# untitled.net
KiCad netlist of a schematic drawn in EAGLE
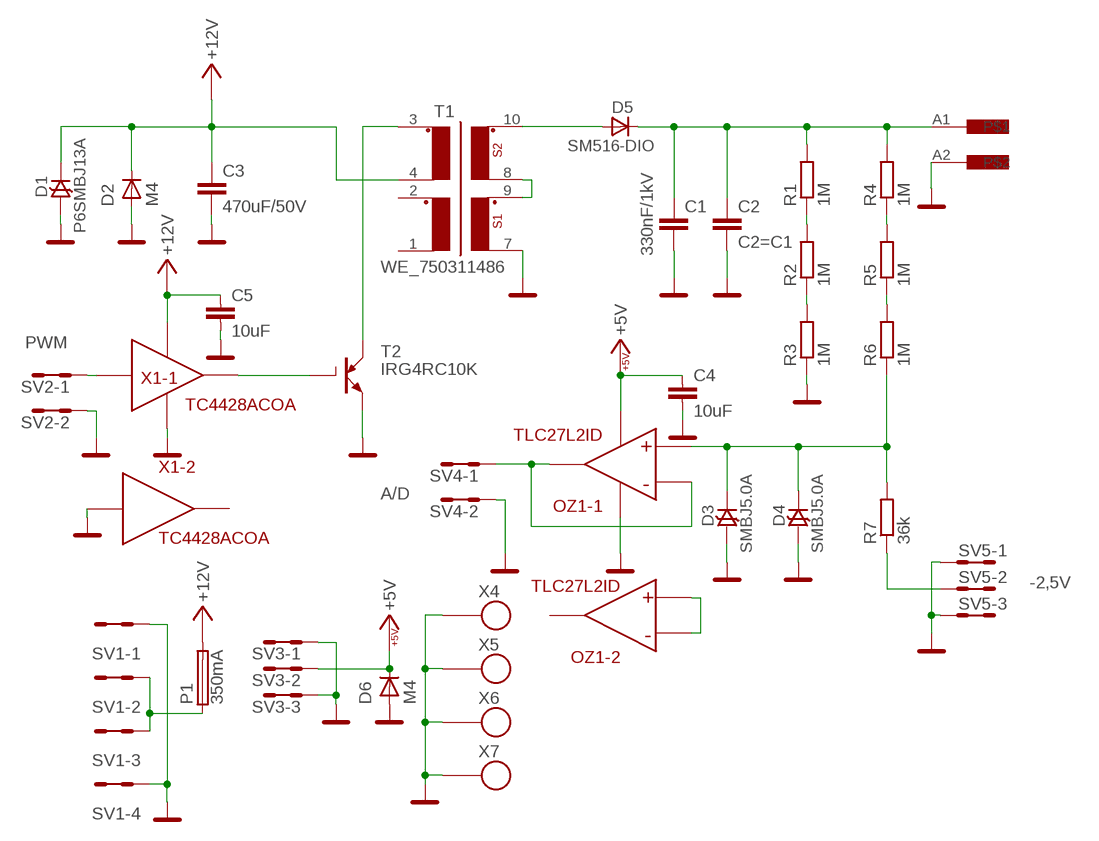
[diagram p0: schematic, sheet 1]

(export (version "E")
  (design (tool "Eeschema 10.0.6"))
  (components
    (comp (ref "C1")
      (value "330nF/1kV")
      (footprint "eagle-import:C22,5MM")
      (libsource (lib "eagle-import") (part "C-22,5MM"))
    )
    (comp (ref "C2")
      (value "C2=C1")
      (footprint "eagle-import:C27,5MM")
      (libsource (lib "eagle-import") (part "C-27,5MM"))
    )
    (comp (ref "C3")
      (value "470uF/50V")
      (footprint "eagle-import:C050-025X075")
      (libsource (lib "eagle-import") (part "C-EU050-025X075"))
    )
    (comp (ref "C4")
      (value "10uF")
      (footprint "eagle-import:C0805")
      (libsource (lib "eagle-import") (part "C0805"))
    )
    (comp (ref "C5")
      (value "10uF")
      (footprint "eagle-import:C0805")
      (libsource (lib "eagle-import") (part "C0805"))
    )
    (comp (ref "D1")
      (value "P6SMBJ13A")
      (footprint "eagle-import:SMB")
      (libsource (lib "eagle-import") (part "D-TRANSIL"))
    )
    (comp (ref "D2")
      (value "M4")
      (footprint "eagle-import:SMA")
      (libsource (lib "eagle-import") (part "D-OB.SMA"))
    )
    (comp (ref "D3")
      (value "SMBJ5.0A")
      (footprint "eagle-import:SMA")
      (libsource (lib "eagle-import") (part "D-TRANSIL-SMA"))
    )
    (comp (ref "D4")
      (value "SMBJ5.0A")
      (footprint "eagle-import:SMA")
      (libsource (lib "eagle-import") (part "D-TRANSIL-SMA"))
    )
    (comp (ref "D5")
      (value "SM516-DIO")
      (footprint "eagle-import:MELF")
      (libsource (lib "eagle-import") (part "D-OB-MELF"))
    )
    (comp (ref "D6")
      (value "M4")
      (footprint "eagle-import:SMA")
      (libsource (lib "eagle-import") (part "D-OB.SMA"))
    )
    (comp (ref "OZ1")
      (value "TLC27L2ID")
      (footprint "eagle-import:SOP8")
      (libsource (lib "eagle-import") (part "TLC27L2"))
    )
    (comp (ref "P1")
      (value "350mA")
      (footprint "eagle-import:1812")
      (libsource (lib "eagle-import") (part "POJISTKA_1812"))
    )
    (comp (ref "R1")
      (value "1M")
      (footprint "eagle-import:1206")
      (libsource (lib "eagle-import") (part "R1206"))
    )
    (comp (ref "R2")
      (value "1M")
      (footprint "eagle-import:1206")
      (libsource (lib "eagle-import") (part "R1206"))
    )
    (comp (ref "R3")
      (value "1M")
      (footprint "eagle-import:1206")
      (libsource (lib "eagle-import") (part "R1206"))
    )
    (comp (ref "R4")
      (value "1M")
      (footprint "eagle-import:1206")
      (libsource (lib "eagle-import") (part "R1206"))
    )
    (comp (ref "R5")
      (value "1M")
      (footprint "eagle-import:1206")
      (libsource (lib "eagle-import") (part "R1206"))
    )
    (comp (ref "R6")
      (value "1M")
      (footprint "eagle-import:1206")
      (libsource (lib "eagle-import") (part "R1206"))
    )
    (comp (ref "R7")
      (value "36k")
      (footprint "eagle-import:0805")
      (libsource (lib "eagle-import") (part "R0805"))
    )
    (comp (ref "SV1")
      (value "MA04-2")
      (footprint "eagle-import:MA04-2")
      (libsource (lib "eagle-import") (part "MA04-2"))
    )
    (comp (ref "SV2")
      (value "MA02-2")
      (footprint "eagle-import:MA02-2")
      (libsource (lib "eagle-import") (part "MA02-2"))
    )
    (comp (ref "SV3")
      (value "MA03-2")
      (footprint "eagle-import:MA03-2")
      (libsource (lib "eagle-import") (part "MA03-2"))
    )
    (comp (ref "SV4")
      (value "MA02-2")
      (footprint "eagle-import:MA02-2")
      (libsource (lib "eagle-import") (part "MA02-2"))
    )
    (comp (ref "SV5")
      (value "MA03-2")
      (footprint "eagle-import:MA03-2")
      (libsource (lib "eagle-import") (part "MA03-2"))
    )
    (comp (ref "T1")
      (value "WE_750311486")
      (footprint "eagle-import:TRAFO75311486")
      (libsource (lib "eagle-import") (part "TRAFO_WE_750311486"))
    )
    (comp (ref "T2")
      (value "IRG4RC10K")
      (footprint "eagle-import:DPAK")
      (libsource (lib "eagle-import") (part "IRG4RC10"))
    )
    (comp (ref "X1")
      (value "TC4428ACOA")
      (footprint "eagle-import:SO8")
      (libsource (lib "eagle-import") (part "TC4428A"))
    )
    (comp (ref "X2")
      (value "SVORKOVNICE2X_PC")
      (footprint "eagle-import:SVORKOVNICE_10,16MM")
      (libsource (lib "eagle-import") (part "SVORKOVNICE2X_PC"))
    )
    (comp (ref "X4")
      (value "SROUB3M")
      (footprint "eagle-import:SROUB3M")
      (libsource (lib "eagle-import") (part "SROUB3M"))
    )
    (comp (ref "X5")
      (value "SROUB3M")
      (footprint "eagle-import:SROUB3M")
      (libsource (lib "eagle-import") (part "SROUB3M"))
    )
    (comp (ref "X6")
      (value "SROUB3M")
      (footprint "eagle-import:SROUB3M")
      (libsource (lib "eagle-import") (part "SROUB3M"))
    )
    (comp (ref "X7")
      (value "SROUB3M")
      (footprint "eagle-import:SROUB3M")
      (libsource (lib "eagle-import") (part "SROUB3M"))
    )
  )
  (nets
    (net (code "1") (name "+5V") (class "Default")
      (node (ref "C4") (pin "1") (pinfunction "1_1") (pintype "passive"))
      (node (ref "D6") (pin "K") (pinfunction "C_K") (pintype "passive"))
      (node (ref "OZ1") (pin "4") (pinfunction "GND_4") (pintype "bidirectional"))
      (node (ref "SV3") (pin "3") (pinfunction "K_3") (pintype "passive"))
      (node (ref "SV3") (pin "4") (pinfunction "K_4") (pintype "passive"))
    )
    (net (code "2") (name "+12V") (class "Default")
      (node (ref "C3") (pin "1") (pinfunction "1_1") (pintype "passive"))
      (node (ref "C5") (pin "1") (pinfunction "1_1") (pintype "passive"))
      (node (ref "D1") (pin "K") (pinfunction "K_K") (pintype "passive"))
      (node (ref "D2") (pin "K") (pinfunction "C_K") (pintype "passive"))
      (node (ref "P1") (pin "2") (pinfunction "2_2") (pintype "passive"))
      (node (ref "T1") (pin "4") (pinfunction "4_4") (pintype "passive"))
      (node (ref "X1") (pin "6") (pinfunction "VDD_6") (pintype "bidirectional"))
    )
    (net (code "3") (name "GND") (class "Default")
      (node (ref "C1") (pin "P$3") (pinfunction "2_P$3") (pintype "passive"))
      (node (ref "C2") (pin "P$2") (pinfunction "2_P$2") (pintype "passive"))
      (node (ref "C3") (pin "2") (pinfunction "2_2") (pintype "passive"))
      (node (ref "C4") (pin "2") (pinfunction "2_2") (pintype "passive"))
      (node (ref "C5") (pin "2") (pinfunction "2_2") (pintype "passive"))
      (node (ref "D1") (pin "A") (pinfunction "A_A") (pintype "passive"))
      (node (ref "D2") (pin "A") (pinfunction "A_A") (pintype "passive"))
      (node (ref "D3") (pin "A") (pinfunction "A_A") (pintype "passive"))
      (node (ref "D4") (pin "A") (pinfunction "A_A") (pintype "passive"))
      (node (ref "D6") (pin "A") (pinfunction "A_A") (pintype "passive"))
      (node (ref "OZ1") (pin "8") (pinfunction "VDD_8") (pintype "bidirectional"))
      (node (ref "R3") (pin "1") (pinfunction "1_1") (pintype "passive"))
      (node (ref "SV1") (pin "1") (pinfunction "K_1") (pintype "passive"))
      (node (ref "SV1") (pin "2") (pinfunction "K_2") (pintype "passive"))
      (node (ref "SV1") (pin "7") (pinfunction "K_7") (pintype "passive"))
      (node (ref "SV1") (pin "8") (pinfunction "K_8") (pintype "passive"))
      (node (ref "SV2") (pin "3") (pinfunction "K_3") (pintype "passive"))
      (node (ref "SV2") (pin "4") (pinfunction "K_4") (pintype "passive"))
      (node (ref "SV3") (pin "1") (pinfunction "K_1") (pintype "passive"))
      (node (ref "SV3") (pin "2") (pinfunction "K_2") (pintype "passive"))
      (node (ref "SV3") (pin "5") (pinfunction "K_5") (pintype "passive"))
      (node (ref "SV3") (pin "6") (pinfunction "K_6") (pintype "passive"))
      (node (ref "SV4") (pin "3") (pinfunction "K_3") (pintype "passive"))
      (node (ref "SV4") (pin "4") (pinfunction "K_4") (pintype "passive"))
      (node (ref "SV5") (pin "1") (pinfunction "K_1") (pintype "passive"))
      (node (ref "SV5") (pin "2") (pinfunction "K_2") (pintype "passive"))
      (node (ref "SV5") (pin "5") (pinfunction "K_5") (pintype "passive"))
      (node (ref "SV5") (pin "6") (pinfunction "K_6") (pintype "passive"))
      (node (ref "T1") (pin "7") (pinfunction "7_7") (pintype "passive"))
      (node (ref "T2") (pin "S") (pinfunction "E_S") (pintype "passive"))
      (node (ref "X1") (pin "3") (pinfunction "GND_3") (pintype "bidirectional"))
      (node (ref "X1") (pin "4") (pinfunction "-_4") (pintype "bidirectional"))
      (node (ref "X2") (pin "A2") (pinfunction "P$2_A2") (pintype "bidirectional"))
      (node (ref "X4") (pin "P$1") (pinfunction "P$1_P$1") (pintype "bidirectional"))
      (node (ref "X5") (pin "P$1") (pinfunction "P$1_P$1") (pintype "bidirectional"))
      (node (ref "X6") (pin "P$1") (pinfunction "P$1_P$1") (pintype "bidirectional"))
      (node (ref "X7") (pin "P$1") (pinfunction "P$1_P$1") (pintype "bidirectional"))
    )
    (net (code "4") (name "Net-(C1-1)") (class "Default")
      (node (ref "C1") (pin "P$2") (pinfunction "1_P$2") (pintype "passive"))
      (node (ref "C2") (pin "P$1") (pinfunction "1_P$1") (pintype "passive"))
      (node (ref "D5") (pin "C") (pinfunction "K_C") (pintype "passive"))
      (node (ref "R1") (pin "2") (pinfunction "2_2") (pintype "passive"))
      (node (ref "R4") (pin "2") (pinfunction "2_2") (pintype "passive"))
      (node (ref "X2") (pin "A1") (pinfunction "P$1_A1") (pintype "bidirectional"))
    )
    (net (code "5") (name "Net-(D5-PadA)") (class "Default")
      (node (ref "D5") (pin "A") (pinfunction "A_A") (pintype "passive"))
      (node (ref "T1") (pin "10") (pinfunction "10_10") (pintype "passive"))
    )
    (net (code "6") (name "Net-(OZ1A-+)") (class "Default")
      (node (ref "D3") (pin "K") (pinfunction "K_K") (pintype "passive"))
      (node (ref "D4") (pin "K") (pinfunction "K_K") (pintype "passive"))
      (node (ref "OZ1") (pin "3") (pinfunction "+_3") (pintype "bidirectional"))
      (node (ref "R6") (pin "1") (pinfunction "1_1") (pintype "passive"))
      (node (ref "R7") (pin "2") (pinfunction "2_2") (pintype "passive"))
    )
    (net (code "7") (name "Net-(OZ1A--)") (class "Default")
      (node (ref "OZ1") (pin "1") (pinfunction "VOUT_1") (pintype "bidirectional"))
      (node (ref "OZ1") (pin "2") (pinfunction "-_2") (pintype "bidirectional"))
      (node (ref "SV4") (pin "1") (pinfunction "K_1") (pintype "passive"))
      (node (ref "SV4") (pin "2") (pinfunction "K_2") (pintype "passive"))
    )
    (net (code "8") (name "Net-(OZ1B-+)") (class "Default")
      (node (ref "OZ1") (pin "5") (pinfunction "+_5") (pintype "bidirectional"))
      (node (ref "OZ1") (pin "6") (pinfunction "-_6") (pintype "bidirectional"))
    )
    (net (code "9") (name "Net-(P1-Pad1)") (class "Default")
      (node (ref "P1") (pin "1") (pinfunction "1_1") (pintype "passive"))
      (node (ref "SV1") (pin "3") (pinfunction "K_3") (pintype "passive"))
      (node (ref "SV1") (pin "4") (pinfunction "K_4") (pintype "passive"))
      (node (ref "SV1") (pin "5") (pinfunction "K_5") (pintype "passive"))
      (node (ref "SV1") (pin "6") (pinfunction "K_6") (pintype "passive"))
    )
    (net (code "10") (name "Net-(R1-Pad1)") (class "Default")
      (node (ref "R1") (pin "1") (pinfunction "1_1") (pintype "passive"))
      (node (ref "R2") (pin "2") (pinfunction "2_2") (pintype "passive"))
    )
    (net (code "11") (name "Net-(R2-Pad1)") (class "Default")
      (node (ref "R2") (pin "1") (pinfunction "1_1") (pintype "passive"))
      (node (ref "R3") (pin "2") (pinfunction "2_2") (pintype "passive"))
    )
    (net (code "12") (name "Net-(R4-Pad1)") (class "Default")
      (node (ref "R4") (pin "1") (pinfunction "1_1") (pintype "passive"))
      (node (ref "R5") (pin "2") (pinfunction "2_2") (pintype "passive"))
    )
    (net (code "13") (name "Net-(R5-Pad1)") (class "Default")
      (node (ref "R5") (pin "1") (pinfunction "1_1") (pintype "passive"))
      (node (ref "R6") (pin "2") (pinfunction "2_2") (pintype "passive"))
    )
    (net (code "14") (name "Net-(R7-Pad1)") (class "Default")
      (node (ref "R7") (pin "1") (pinfunction "1_1") (pintype "passive"))
      (node (ref "SV5") (pin "3") (pinfunction "K_3") (pintype "passive"))
      (node (ref "SV5") (pin "4") (pinfunction "K_4") (pintype "passive"))
    )
    (net (code "15") (name "Net-(T1-Pad8)") (class "Default")
      (node (ref "T1") (pin "8") (pinfunction "8_8") (pintype "passive"))
      (node (ref "T1") (pin "9") (pinfunction "9_9") (pintype "passive"))
    )
    (net (code "16") (name "Net-(T2-C)") (class "Default")
      (node (ref "T1") (pin "3") (pinfunction "3_3") (pintype "passive"))
      (node (ref "T2") (pin "D") (pinfunction "C_D") (pintype "passive"))
    )
    (net (code "17") (name "Net-(X1A--)") (class "Default")
      (node (ref "SV2") (pin "1") (pinfunction "K_1") (pintype "passive"))
      (node (ref "SV2") (pin "2") (pinfunction "K_2") (pintype "passive"))
      (node (ref "X1") (pin "2") (pinfunction "-_2") (pintype "bidirectional"))
    )
    (net (code "18") (name "Net-(X1A-VOUT)") (class "Default")
      (node (ref "T2") (pin "G") (pinfunction "G_G") (pintype "passive"))
      (node (ref "X1") (pin "7") (pinfunction "VOUT_7") (pintype "bidirectional"))
    )
    (net (code "19") (name "unconnected-(OZ1B-VOUT-Pad7)") (class "Default")
      (node (ref "OZ1") (pin "7") (pinfunction "VOUT_7") (pintype "bidirectional"))
    )
    (net (code "20") (name "unconnected-(T1-Pad1)") (class "Default")
      (node (ref "T1") (pin "1") (pinfunction "1_1") (pintype "passive"))
    )
    (net (code "21") (name "unconnected-(T1-Pad2)") (class "Default")
      (node (ref "T1") (pin "2") (pinfunction "2_2") (pintype "passive"))
    )
    (net (code "22") (name "unconnected-(X1B-VOUT-Pad5)") (class "Default")
      (node (ref "X1") (pin "5") (pinfunction "VOUT_5") (pintype "bidirectional"))
    )
  )
)
